# Power.net
KiCad netlist of a schematic drawn in Altium Designer
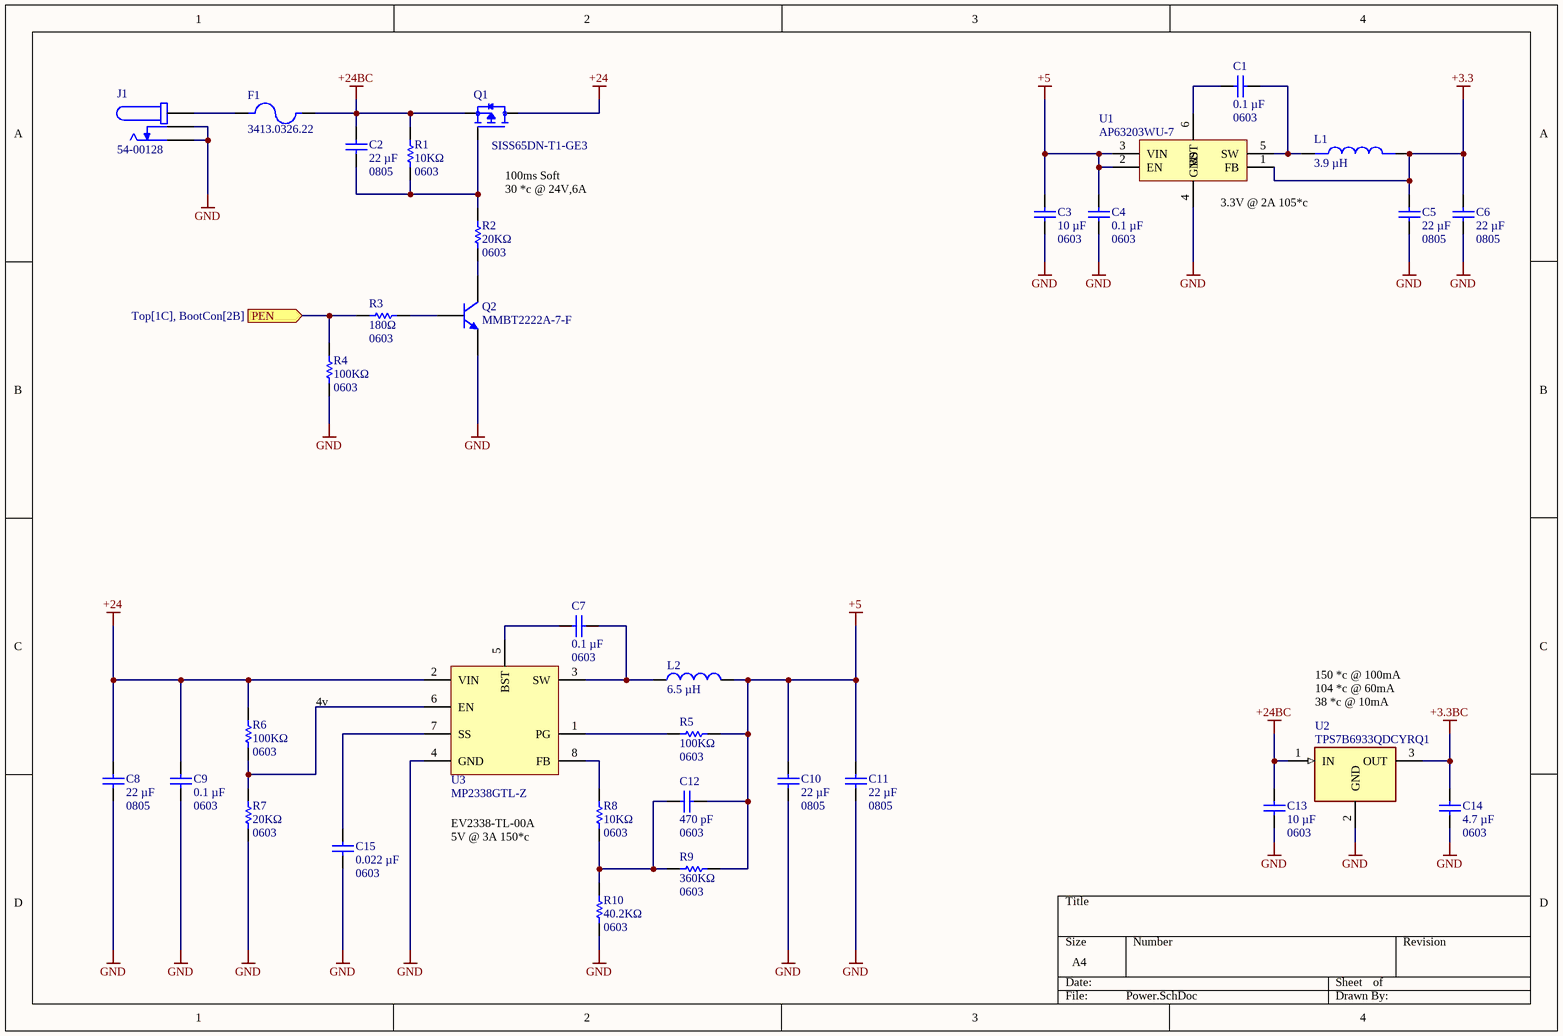
[diagram p0: Power.SchDoc]

(export (version "E")
  (design (tool "Eeschema 10.0.6"))
  (components
    (comp (ref "C1")
      (value "0.1 µF")
      (footprint "0603")
      (description "0.1 µF ±20% 100V Ceramic Capacitor X7R 0603 (1608 Metric)")
      (fields (field (name "CASE") "0603") (field (name "TOLERANCE") "±20%") (field (name "VOLTAGE") "100V"))
      (libsource (lib "Murata Electronics") (part "GRM188R72A104MA35J"))
    )
    (comp (ref "C2")
      (value "22 µF")
      (footprint "0805")
      (description "CAP CER 22UF 35V X5R 0805")
      (fields (field (name "TOLERANCE") "±20%") (field (name "VOLTAGE") "35V") (field (name "CASE") "0805"))
      (libsource (lib "TDK Corporation") (part "C2012X5R1V226M125AC"))
    )
    (comp (ref "C3")
      (value "10 µF")
      (footprint "0603")
      (description "10 µF ±20% 35V Ceramic Capacitor X5R 0603 (1608 Metric)")
      (fields (field (name "CASE") "0603") (field (name "TOLERANCE") "±20%") (field (name "VOLTAGE") "35V"))
      (libsource (lib "Murata Electronics") (part "GRM188R6YA106MA73D"))
    )
    (comp (ref "C4")
      (value "0.1 µF")
      (footprint "0603")
      (description "0.1 µF ±20% 100V Ceramic Capacitor X7R 0603 (1608 Metric)")
      (fields (field (name "CASE") "0603") (field (name "TOLERANCE") "±20%") (field (name "VOLTAGE") "100V"))
      (libsource (lib "Murata Electronics") (part "GRM188R72A104MA35J"))
    )
    (comp (ref "C5")
      (value "22 µF")
      (footprint "0805")
      (description "CAP CER 22UF 35V X5R 0805")
      (fields (field (name "TOLERANCE") "±20%") (field (name "VOLTAGE") "35V") (field (name "CASE") "0805"))
      (libsource (lib "TDK Corporation") (part "C2012X5R1V226M125AC"))
    )
    (comp (ref "C6")
      (value "22 µF")
      (footprint "0805")
      (description "CAP CER 22UF 35V X5R 0805")
      (fields (field (name "TOLERANCE") "±20%") (field (name "VOLTAGE") "35V") (field (name "CASE") "0805"))
      (libsource (lib "TDK Corporation") (part "C2012X5R1V226M125AC"))
    )
    (comp (ref "C7")
      (value "0.1 µF")
      (footprint "0603")
      (description "0.1 µF ±20% 100V Ceramic Capacitor X7R 0603 (1608 Metric)")
      (fields (field (name "CASE") "0603") (field (name "TOLERANCE") "±20%") (field (name "VOLTAGE") "100V"))
      (libsource (lib "Murata Electronics") (part "GRM188R72A104MA35J"))
    )
    (comp (ref "C8")
      (value "22 µF")
      (footprint "0805")
      (description "CAP CER 22UF 35V X5R 0805")
      (fields (field (name "TOLERANCE") "±20%") (field (name "VOLTAGE") "35V") (field (name "CASE") "0805"))
      (libsource (lib "TDK Corporation") (part "C2012X5R1V226M125AC"))
    )
    (comp (ref "C9")
      (value "0.1 µF")
      (footprint "0603")
      (description "0.1 µF ±20% 100V Ceramic Capacitor X7R 0603 (1608 Metric)")
      (fields (field (name "CASE") "0603") (field (name "TOLERANCE") "±20%") (field (name "VOLTAGE") "100V"))
      (libsource (lib "Murata Electronics") (part "GRM188R72A104MA35J"))
    )
    (comp (ref "C10")
      (value "22 µF")
      (footprint "0805")
      (description "CAP CER 22UF 35V X5R 0805")
      (fields (field (name "TOLERANCE") "±20%") (field (name "VOLTAGE") "35V") (field (name "CASE") "0805"))
      (libsource (lib "TDK Corporation") (part "C2012X5R1V226M125AC"))
    )
    (comp (ref "C11")
      (value "22 µF")
      (footprint "0805")
      (description "CAP CER 22UF 35V X5R 0805")
      (fields (field (name "TOLERANCE") "±20%") (field (name "VOLTAGE") "35V") (field (name "CASE") "0805"))
      (libsource (lib "TDK Corporation") (part "C2012X5R1V226M125AC"))
    )
    (comp (ref "C12")
      (value "470 pF")
      (footprint "0603")
      (description "470 pF ±5% 100V Ceramic Capacitor C0G, NP0 0603 (1608 Metric)")
      (fields (field (name "CASE") "0603") (field (name "TOLERANCE") "±5%") (field (name "VOLTAGE") "100V"))
      (libsource (lib "Murata Electronics") (part "GRM1885C2A471JA01D"))
    )
    (comp (ref "C13")
      (value "10 µF")
      (footprint "0603")
      (description "10 µF ±20% 35V Ceramic Capacitor X5R 0603 (1608 Metric)")
      (fields (field (name "CASE") "0603") (field (name "TOLERANCE") "±20%") (field (name "VOLTAGE") "35V"))
      (libsource (lib "Murata Electronics") (part "GRM188R6YA106MA73D"))
    )
    (comp (ref "C14")
      (value "4.7 µF")
      (footprint "0603")
      (description "4.7 µF ±10% 35V Ceramic Capacitor X5R 0603 (1608 Metric)")
      (fields (field (name "CASE") "0603") (field (name "TOLERANCE") "±10%") (field (name "VOLTAGE") "35V"))
      (libsource (lib "Murata Electronics") (part "GRM188R6YA475KE15D"))
    )
    (comp (ref "C15")
      (value "0.022 µF")
      (footprint "0603")
      (description "0.022 µF ±10% 100V Ceramic Capacitor X7R 0603 (1608 Metric)")
      (fields (field (name "CASE") "0603") (field (name "TOLERANCE") "±10%") (field (name "VOLTAGE") "100V"))
      (libsource (lib "Murata Electronics") (part "GRM188R72A223KAC4D"))
    )
    (comp (ref "F1")
      (value "3413.0326.22")
      (footprint "1206")
      (description "7 A 32 V AC 63 V DC Fuse Board Mount (Cartridge Style Excluded) Surface Mount 1206 (3216 Metric)")
      (libsource (lib "SCHURTER Inc") (part "3413.0326.22"))
    )
    (comp (ref "J1")
      (value "54-00128")
      (footprint "5.5X2.5MM")
      (description "Power Barrel Connector Jack 2.50mm ID (0.098\"), 5.50mm OD (0.217\") Through Hole, Right Angle")
      (fields (field (name "VOLTAGE") "48V"))
      (libsource (lib "Tensility International Corp") (part "54-00128"))
    )
    (comp (ref "L1")
      (value "3.9 µH")
      (footprint "6.30mm x 6.30mm")
      (description "3.9 µH Shielded Drum Core, Wirewound Inductor 4.2 A 22mOhm Nonstandard")
      (fields (field (name "Comment") "1255AY-3R9N=P3"))
      (libsource (lib "Murata Electronics") (part "1255AY-3R9N=P3"))
    )
    (comp (ref "L2")
      (value "6.5 µH")
      (footprint "7.00mm x 6.90mm")
      (description "6.5 µH Shielded Wirewound Inductor 6 A 21.5mOhm Nonstandard")
      (fields (field (name "Comment") "744314650"))
      (libsource (lib "Wurth Elektronik WE-HCI") (part "744314650"))
    )
    (comp (ref "Q1")
      (value "SISS65DN-T1-GE3")
      (footprint "PowerPAK® 1212-8S")
      (description "P-Channel 30 V 25.9A (Ta), 94A (Tc) 5.1W (Ta), 65.8W (Tc) Surface Mount PowerPAK® 1212-8S")
      (libsource (lib "Vishay Siliconix") (part "SISS65DN-T1-GE3"))
    )
    (comp (ref "Q2")
      (value "MMBT2222A-7-F")
      (footprint "SOT-23-3")
      (description "Bipolar (BJT) Transistor NPN 40 V 600 mA 300MHz 310 mW Surface Mount SOT-23-3")
      (libsource (lib "Diodes Incorporated") (part "MMBT2222A-7-F"))
    )
    (comp (ref "R1")
      (value "10KΩ")
      (footprint "0603")
      (description "10 kOhms ±1% 0.1W, 1/10W Chip Resistor 0603 (1608 Metric) Automotive AEC-Q200 Thick Film")
      (fields (field (name "CASE") "0603") (field (name "TOLERANCE") "1%") (field (name "POWER") "0.1W"))
      (libsource (lib "Stackpole Electronics Inc") (part "RMCF0603FG10K0"))
    )
    (comp (ref "R2")
      (value "20KΩ")
      (footprint "0603")
      (description "20 kOhms ±1% 0.1W, 1/10W Chip Resistor 0603 (1608 Metric) Automotive AEC-Q200 Thick Film")
      (fields (field (name "CASE") "0603") (field (name "TOLERANCE") "1%") (field (name "POWER") "0.1W"))
      (libsource (lib "Stackpole Electronics Inc") (part "RMCF0603FG20K0"))
    )
    (comp (ref "R3")
      (value "180Ω")
      (footprint "0603")
      (description "180 Ohms ±1% 0.1W, 1/10W Chip Resistor 0603 (1608 Metric) Automotive AEC-Q200 Thick Film")
      (fields (field (name "CASE") "0603") (field (name "TOLERANCE") "1%") (field (name "POWER") "0.1W"))
      (libsource (lib "Stackpole Electronics Inc") (part "RMCF0603FT180R"))
    )
    (comp (ref "R4")
      (value "100KΩ")
      (footprint "0603")
      (description "100 kOhms ±1% 0.1W, 1/10W Chip Resistor 0603 (1608 Metric) Automotive AEC-Q200 Thick Film")
      (fields (field (name "CASE") "0603") (field (name "TOLERANCE") "1%") (field (name "POWER") "0.1W"))
      (libsource (lib "Stackpole Electronics Inc") (part "RMCF0603FG100K"))
    )
    (comp (ref "R5")
      (value "100KΩ")
      (footprint "0603")
      (description "100 kOhms ±1% 0.1W, 1/10W Chip Resistor 0603 (1608 Metric) Automotive AEC-Q200 Thick Film")
      (fields (field (name "CASE") "0603") (field (name "TOLERANCE") "1%") (field (name "POWER") "0.1W"))
      (libsource (lib "Stackpole Electronics Inc") (part "RMCF0603FG100K"))
    )
    (comp (ref "R6")
      (value "100KΩ")
      (footprint "0603")
      (description "100 kOhms ±1% 0.1W, 1/10W Chip Resistor 0603 (1608 Metric) Automotive AEC-Q200 Thick Film")
      (fields (field (name "CASE") "0603") (field (name "TOLERANCE") "1%") (field (name "POWER") "0.1W"))
      (libsource (lib "Stackpole Electronics Inc") (part "RMCF0603FG100K"))
    )
    (comp (ref "R7")
      (value "20KΩ")
      (footprint "0603")
      (description "20 kOhms ±1% 0.1W, 1/10W Chip Resistor 0603 (1608 Metric) Automotive AEC-Q200 Thick Film")
      (fields (field (name "CASE") "0603") (field (name "TOLERANCE") "1%") (field (name "POWER") "0.1W"))
      (libsource (lib "Stackpole Electronics Inc") (part "RMCF0603FG20K0"))
    )
    (comp (ref "R8")
      (value "10KΩ")
      (footprint "0603")
      (description "10 kOhms ±1% 0.1W, 1/10W Chip Resistor 0603 (1608 Metric) Automotive AEC-Q200 Thick Film")
      (fields (field (name "CASE") "0603") (field (name "TOLERANCE") "1%") (field (name "POWER") "0.1W"))
      (libsource (lib "Stackpole Electronics Inc") (part "RMCF0603FG10K0"))
    )
    (comp (ref "R9")
      (value "360KΩ")
      (footprint "0603")
      (description "360 kOhms ±1% 0.1W, 1/10W Chip Resistor 0603 (1608 Metric) Automotive AEC-Q200 Thick Film")
      (fields (field (name "CASE") "0603") (field (name "TOLERANCE") "1%") (field (name "POWER") "0.1W"))
      (libsource (lib "Stackpole Electronics Inc") (part "RMCF0603FT360K"))
    )
    (comp (ref "R10")
      (value "40.2KΩ")
      (footprint "0603")
      (description "40.2 kOhms ±1% 0.1W, 1/10W Chip Resistor 0603 (1608 Metric) Automotive AEC-Q200 Thick Film")
      (fields (field (name "CASE") "0603") (field (name "TOLERANCE") "1%") (field (name "POWER") "0.1W"))
      (libsource (lib "Stackpole Electronics Inc") (part "RMCF0603FT40K2"))
    )
    (comp (ref "U1")
      (value "AP63203WU-7")
      (footprint "TSOT-23-6")
      (description "Buck Switching Regulator IC Positive Fixed 3.3V 1 Output 2A SOT-23-6 Thin, TSOT-23-6")
      (libsource (lib "Diodes Incorporated") (part "AP63203WU-7"))
    )
    (comp (ref "U2")
      (value "TPS7B6933QDCYRQ1")
      (footprint "SOT-223-4")
      (description "Linear Voltage Regulator IC Positive Fixed 1 Output 150mA SOT-223-4")
      (libsource (lib "Texas Instruments") (part "TPS7B6933QDCYRQ1"))
    )
    (comp (ref "U3")
      (value "MP2338GTL-Z")
      (footprint "SOT-583")
      (description "Buck Switching Regulator IC Positive Adjustable 0.5V 1 Output 3A SOT-583")
      (libsource (lib "Monolithic Power Systems Inc") (part "MP2338GTL-Z"))
    )
  )
  (nets
    (net (code "1") (name "+3.3") (class "Default")
      (node (ref "C5") (pin "1") (pinfunction "1_1") (pintype "passive"))
      (node (ref "C6") (pin "1") (pinfunction "1_1") (pintype "passive"))
      (node (ref "L1") (pin "2") (pinfunction "2_2") (pintype "passive"))
      (node (ref "U1") (pin "1") (pinfunction "FB_1") (pintype "passive"))
    )
    (net (code "2") (name "+3.3BC") (class "Default")
      (node (ref "C14") (pin "1") (pinfunction "1_1") (pintype "passive"))
      (node (ref "U2") (pin "3") (pinfunction "OUT_3") (pintype "passive"))
    )
    (net (code "3") (name "+5") (class "Default")
      (node (ref "C10") (pin "1") (pinfunction "1_1") (pintype "passive"))
      (node (ref "C11") (pin "1") (pinfunction "1_1") (pintype "passive"))
      (node (ref "C12") (pin "1") (pinfunction "1_1") (pintype "passive"))
      (node (ref "C3") (pin "2") (pinfunction "2_2") (pintype "passive"))
      (node (ref "C4") (pin "1") (pinfunction "1_1") (pintype "passive"))
      (node (ref "L2") (pin "2") (pinfunction "2_2") (pintype "passive"))
      (node (ref "R5") (pin "1") (pinfunction "1_1") (pintype "passive"))
      (node (ref "R9") (pin "1") (pinfunction "1_1") (pintype "passive"))
      (node (ref "U1") (pin "2") (pinfunction "EN_2") (pintype "passive"))
      (node (ref "U1") (pin "3") (pinfunction "VIN_3") (pintype "passive"))
    )
    (net (code "4") (name "+24") (class "Default")
      (node (ref "C8") (pin "1") (pinfunction "1_1") (pintype "passive"))
      (node (ref "C9") (pin "1") (pinfunction "1_1") (pintype "passive"))
      (node (ref "Q1") (pin "5") (pinfunction "D_5") (pintype "passive"))
      (node (ref "R6") (pin "1") (pinfunction "1_1") (pintype "passive"))
      (node (ref "U3") (pin "2") (pinfunction "VIN_2") (pintype "passive"))
    )
    (net (code "5") (name "+24BC") (class "Default")
      (node (ref "C13") (pin "2") (pinfunction "2_2") (pintype "passive"))
      (node (ref "C2") (pin "1") (pinfunction "1_1") (pintype "passive"))
      (node (ref "F1") (pin "2") (pinfunction "2_2") (pintype "passive"))
      (node (ref "Q1") (pin "1") (pinfunction "S_1") (pintype "passive"))
      (node (ref "R1") (pin "2") (pinfunction "2_2") (pintype "passive"))
      (node (ref "U2") (pin "1") (pinfunction "IN_1") (pintype "input"))
    )
    (net (code "6") (name "/PEN") (class "Default")
      (node (ref "R3") (pin "2") (pinfunction "2_2") (pintype "passive"))
      (node (ref "R4") (pin "1") (pinfunction "1_1") (pintype "passive"))
    )
    (net (code "7") (name "GND") (class "Default")
      (node (ref "C10") (pin "2") (pinfunction "2_2") (pintype "passive"))
      (node (ref "C11") (pin "2") (pinfunction "2_2") (pintype "passive"))
      (node (ref "C13") (pin "1") (pinfunction "1_1") (pintype "passive"))
      (node (ref "C14") (pin "2") (pinfunction "2_2") (pintype "passive"))
      (node (ref "C15") (pin "1") (pinfunction "1_1") (pintype "passive"))
      (node (ref "C3") (pin "1") (pinfunction "1_1") (pintype "passive"))
      (node (ref "C4") (pin "2") (pinfunction "2_2") (pintype "passive"))
      (node (ref "C5") (pin "2") (pinfunction "2_2") (pintype "passive"))
      (node (ref "C6") (pin "2") (pinfunction "2_2") (pintype "passive"))
      (node (ref "C8") (pin "2") (pinfunction "2_2") (pintype "passive"))
      (node (ref "C9") (pin "2") (pinfunction "2_2") (pintype "passive"))
      (node (ref "J1") (pin "B") (pinfunction "B_B") (pintype "passive"))
      (node (ref "J1") (pin "C") (pinfunction "C_C") (pintype "passive"))
      (node (ref "Q2") (pin "2") (pinfunction "E_2") (pintype "passive"))
      (node (ref "R10") (pin "1") (pinfunction "1_1") (pintype "passive"))
      (node (ref "R4") (pin "2") (pinfunction "2_2") (pintype "passive"))
      (node (ref "R7") (pin "2") (pinfunction "2_2") (pintype "passive"))
      (node (ref "U1") (pin "4") (pinfunction "GND_4") (pintype "passive"))
      (node (ref "U2") (pin "2") (pinfunction "GND_2") (pintype "power_in"))
      (node (ref "U3") (pin "4") (pinfunction "GND_4") (pintype "passive"))
    )
    (net (code "8") (name "Net-(C12-Pad2)") (class "Default")
      (node (ref "C12") (pin "2") (pinfunction "2_2") (pintype "passive"))
      (node (ref "R10") (pin "2") (pinfunction "2_2") (pintype "passive"))
      (node (ref "R8") (pin "1") (pinfunction "1_1") (pintype "passive"))
      (node (ref "R9") (pin "2") (pinfunction "2_2") (pintype "passive"))
    )
    (net (code "9") (name "Net-(F1-Pad1)") (class "Default")
      (node (ref "F1") (pin "1") (pinfunction "1_1") (pintype "passive"))
      (node (ref "J1") (pin "A") (pinfunction "A_A") (pintype "passive"))
    )
    (net (code "10") (name "Net-(Q1-G)") (class "Default")
      (node (ref "C2") (pin "2") (pinfunction "2_2") (pintype "passive"))
      (node (ref "Q1") (pin "4") (pinfunction "G_4") (pintype "passive"))
      (node (ref "R1") (pin "1") (pinfunction "1_1") (pintype "passive"))
      (node (ref "R2") (pin "1") (pinfunction "1_1") (pintype "passive"))
    )
    (net (code "11") (name "Net-(Q2-B)") (class "Default")
      (node (ref "Q2") (pin "1") (pinfunction "B_1") (pintype "passive"))
      (node (ref "R3") (pin "1") (pinfunction "1_1") (pintype "passive"))
    )
    (net (code "12") (name "Net-(Q2-C)") (class "Default")
      (node (ref "Q2") (pin "3") (pinfunction "C_3") (pintype "passive"))
      (node (ref "R2") (pin "2") (pinfunction "2_2") (pintype "passive"))
    )
    (net (code "13") (name "Net-(U1-BST)") (class "Default")
      (node (ref "C1") (pin "2") (pinfunction "2_2") (pintype "passive"))
      (node (ref "U1") (pin "6") (pinfunction "BST_6") (pintype "passive"))
    )
    (net (code "14") (name "Net-(U1-SW)") (class "Default")
      (node (ref "C1") (pin "1") (pinfunction "1_1") (pintype "passive"))
      (node (ref "L1") (pin "1") (pinfunction "1_1") (pintype "passive"))
      (node (ref "U1") (pin "5") (pinfunction "SW_5") (pintype "passive"))
    )
    (net (code "15") (name "Net-(U3-BST)") (class "Default")
      (node (ref "C7") (pin "2") (pinfunction "2_2") (pintype "passive"))
      (node (ref "U3") (pin "5") (pinfunction "BST_5") (pintype "passive"))
    )
    (net (code "16") (name "Net-(U3-EN)") (class "Default")
      (node (ref "R6") (pin "2") (pinfunction "2_2") (pintype "passive"))
      (node (ref "R7") (pin "1") (pinfunction "1_1") (pintype "passive"))
      (node (ref "U3") (pin "6") (pinfunction "EN_6") (pintype "passive"))
    )
    (net (code "17") (name "Net-(U3-FB)") (class "Default")
      (node (ref "R8") (pin "2") (pinfunction "2_2") (pintype "passive"))
      (node (ref "U3") (pin "8") (pinfunction "FB_8") (pintype "passive"))
    )
    (net (code "18") (name "Net-(U3-PG)") (class "Default")
      (node (ref "R5") (pin "2") (pinfunction "2_2") (pintype "passive"))
      (node (ref "U3") (pin "1") (pinfunction "PG_1") (pintype "passive"))
    )
    (net (code "19") (name "Net-(U3-SS)") (class "Default")
      (node (ref "C15") (pin "2") (pinfunction "2_2") (pintype "passive"))
      (node (ref "U3") (pin "7") (pinfunction "SS_7") (pintype "passive"))
    )
    (net (code "20") (name "Net-(U3-SW)") (class "Default")
      (node (ref "C7") (pin "1") (pinfunction "1_1") (pintype "passive"))
      (node (ref "L2") (pin "1") (pinfunction "1_1") (pintype "passive"))
      (node (ref "U3") (pin "3") (pinfunction "SW_3") (pintype "passive"))
    )
  )
)
